# Lab_Controller_Board_v08.net
KiCad netlist of a schematic drawn in EAGLE
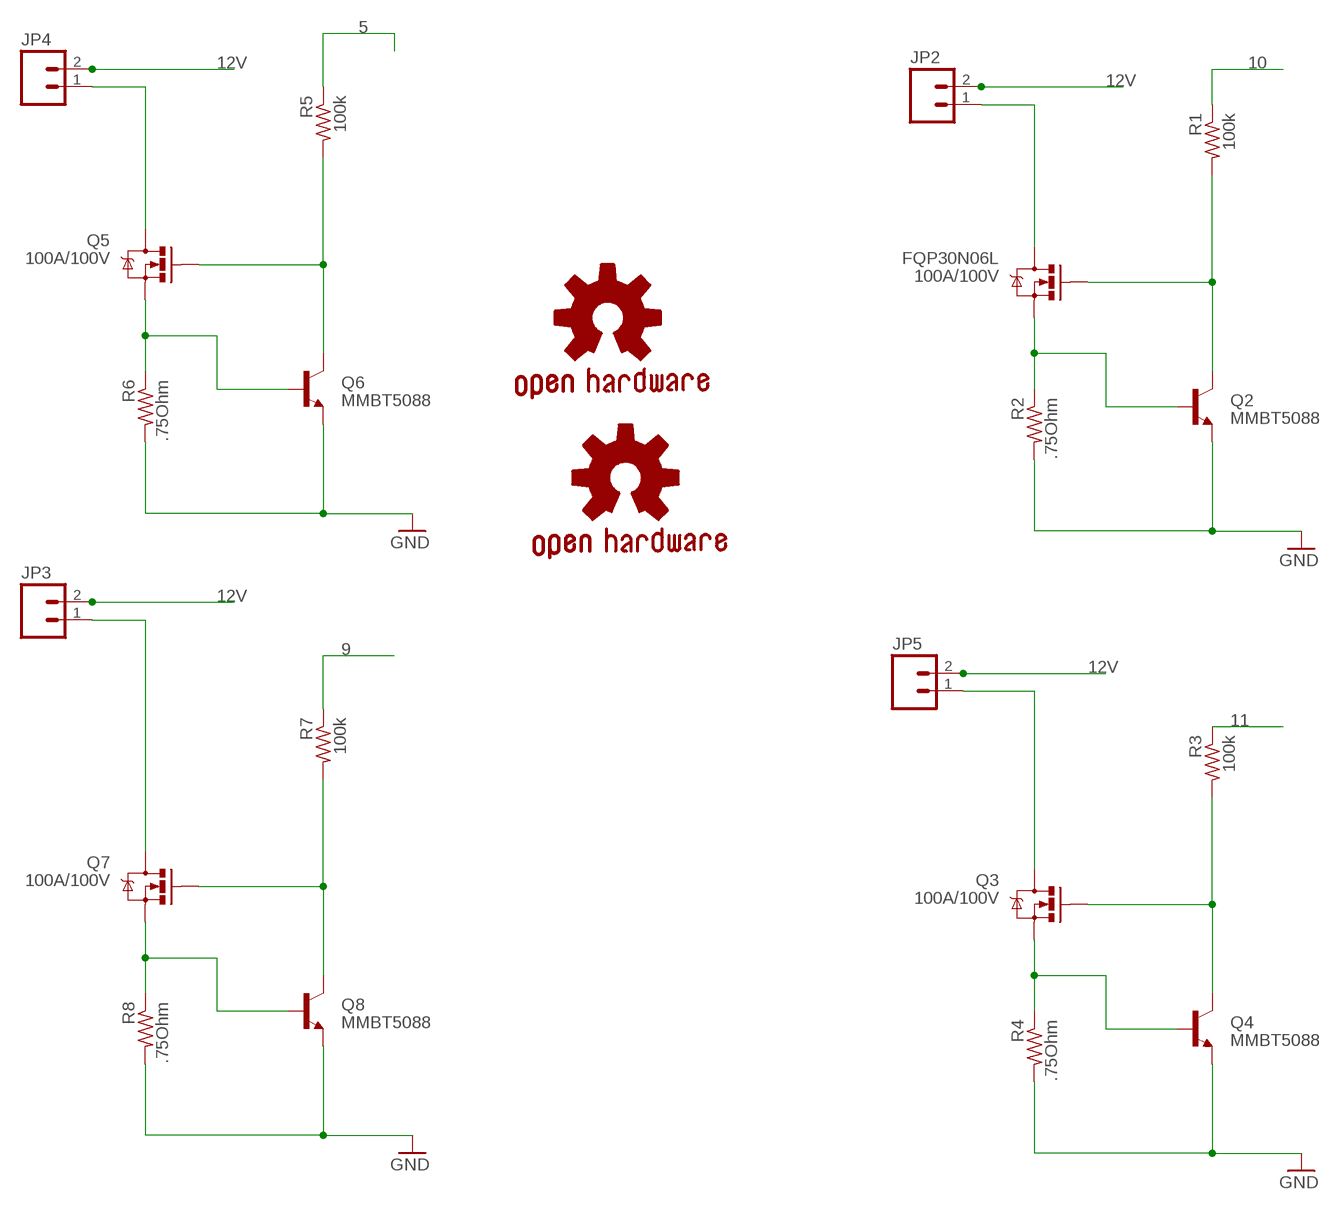
[diagram p0: schematic, sheet 1]
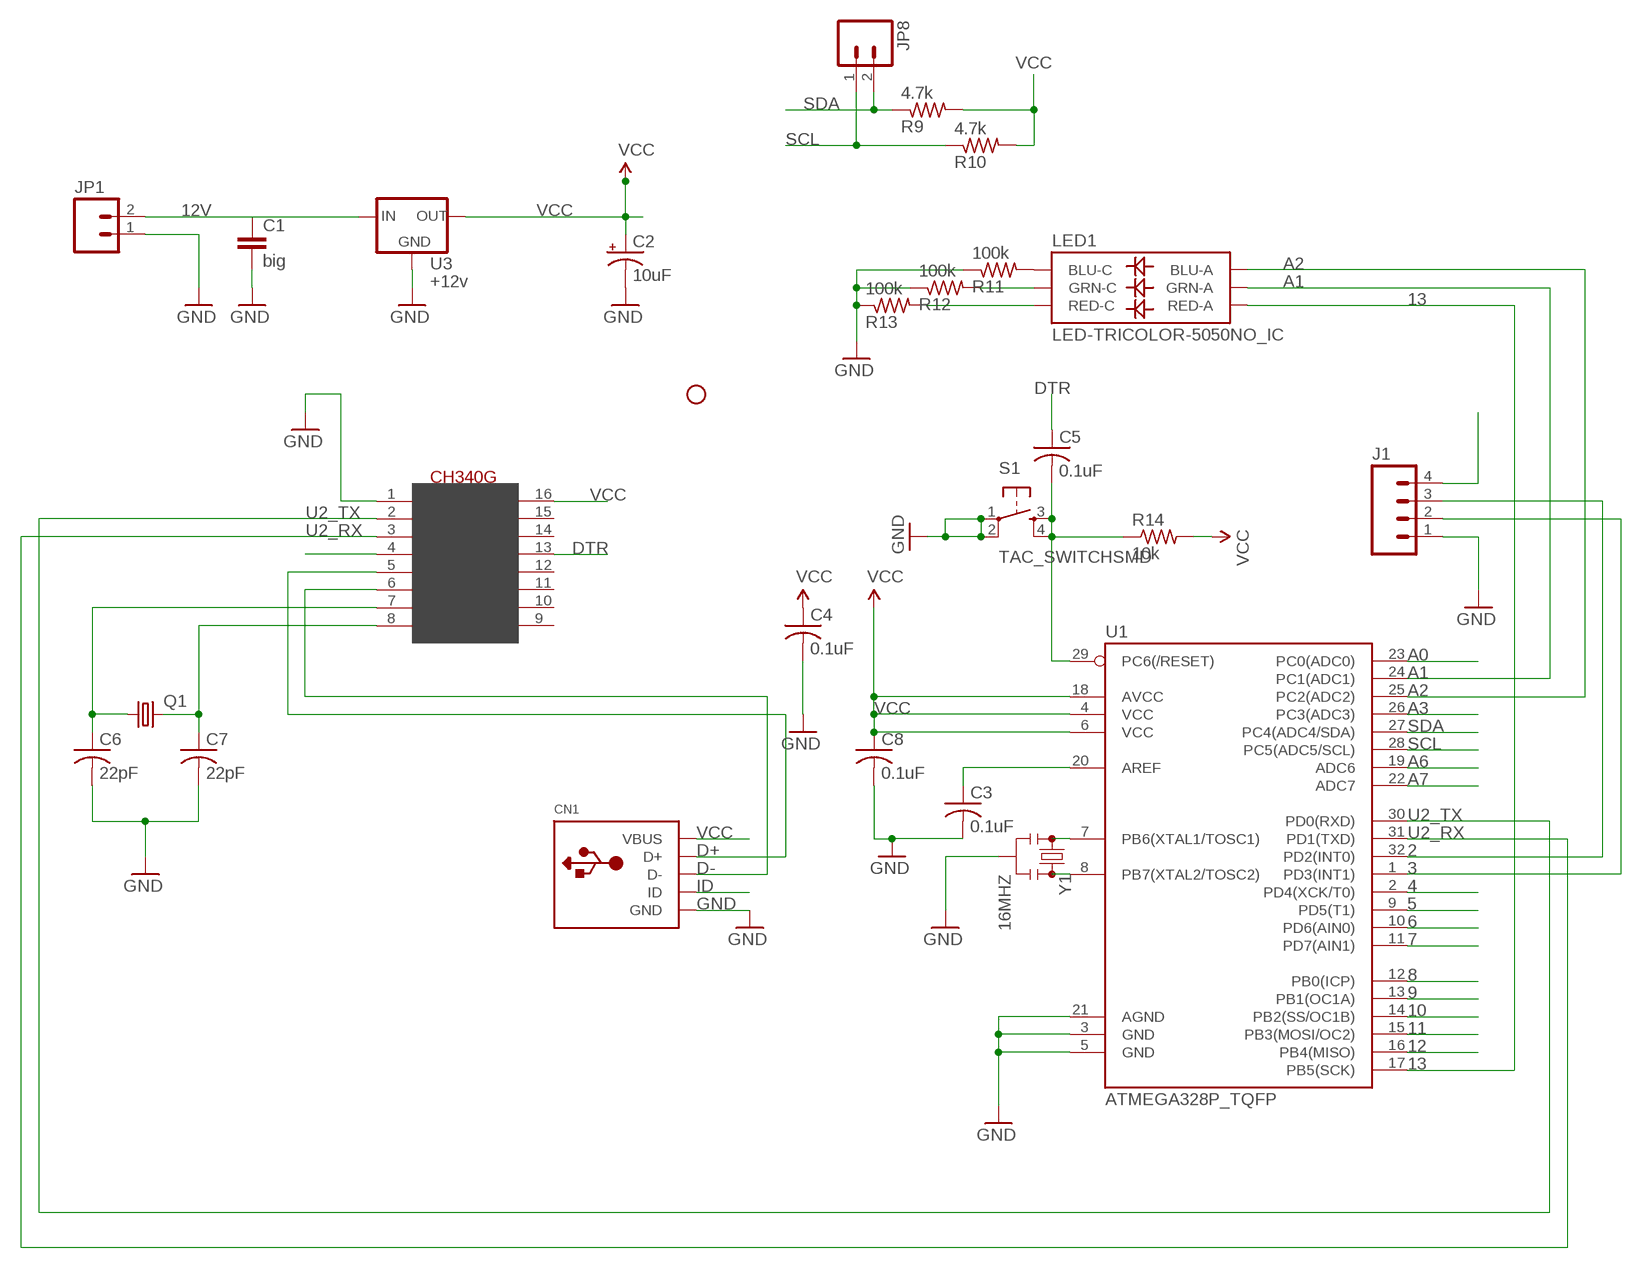
[diagram p1: schematic, sheet 2]

(export (version "E")
  (design (tool "Eeschema 10.0.6"))
  (components
    (comp (ref "C1")
      (value "big")
      (footprint "eagle-import:CAP-PTH-5MM")
      (libsource (lib "eagle-import") (part "CAPPTH1"))
    )
    (comp (ref "C2")
      (value "10uF")
      (footprint "eagle-import:EIA3528")
      (libsource (lib "eagle-import") (part "CAP_POL3528"))
    )
    (comp (ref "C3")
      (value "0.1uF")
      (footprint "eagle-import:C0402")
      (libsource (lib "eagle-import") (part "C-USC0402"))
    )
    (comp (ref "C4")
      (value "0.1uF")
      (footprint "eagle-import:C0402")
      (libsource (lib "eagle-import") (part "C-USC0402"))
    )
    (comp (ref "C5")
      (value "0.1uF")
      (footprint "eagle-import:C0402")
      (libsource (lib "eagle-import") (part "C-USC0402"))
    )
    (comp (ref "C6")
      (value "22pF")
      (footprint "eagle-import:C0402")
      (libsource (lib "eagle-import") (part "C-USC0402"))
    )
    (comp (ref "C7")
      (value "22pF")
      (footprint "eagle-import:C0402")
      (libsource (lib "eagle-import") (part "C-USC0402"))
    )
    (comp (ref "C8")
      (value "0.1uF")
      (footprint "eagle-import:C0402")
      (libsource (lib "eagle-import") (part "C-USC0402"))
    )
    (comp (ref "CN1")
      (value "USBMINIB")
      (footprint "eagle-import:USB-MINIB")
      (libsource (lib "eagle-import") (part "USBMINIB"))
    )
    (comp (ref "J1")
      (value "M04LOCK")
      (footprint "eagle-import:1X04_LOCK")
      (libsource (lib "eagle-import") (part "M04LOCK"))
    )
    (comp (ref "JP1")
      (value "M025MM")
      (footprint "eagle-import:SCREWTERMINAL-5MM-2")
      (libsource (lib "eagle-import") (part "M025MM"))
    )
    (comp (ref "JP8")
      (value "M02LOCK")
      (footprint "eagle-import:1X02_LOCK")
      (libsource (lib "eagle-import") (part "M02LOCK"))
    )
    (comp (ref "LED1")
      (value "LED-TRICOLOR-5050NO_IC")
      (footprint "eagle-import:LED-TRICOLOR-5050")
      (libsource (lib "eagle-import") (part "LED-TRICOLOR-5050NO_IC"))
    )
    (comp (ref "Q1")
      (value "CRYSTALHC49UP")
      (footprint "eagle-import:HC49UP")
      (libsource (lib "eagle-import") (part "CRYSTALHC49UP"))
    )
    (comp (ref "R9")
      (value "4.7k")
      (footprint "eagle-import:M0805")
      (libsource (lib "eagle-import") (part "R-US_M0805"))
    )
    (comp (ref "R10")
      (value "4.7k")
      (footprint "eagle-import:M0805")
      (libsource (lib "eagle-import") (part "R-US_M0805"))
    )
    (comp (ref "R11")
      (value "100k")
      (footprint "eagle-import:R0805W")
      (libsource (lib "eagle-import") (part "R-US_R0805W"))
    )
    (comp (ref "R12")
      (value "100k")
      (footprint "eagle-import:R0805W")
      (libsource (lib "eagle-import") (part "R-US_R0805W"))
    )
    (comp (ref "R13")
      (value "100k")
      (footprint "eagle-import:R0805W")
      (libsource (lib "eagle-import") (part "R-US_R0805W"))
    )
    (comp (ref "R14")
      (value "10k")
      (footprint "eagle-import:R0402")
      (libsource (lib "eagle-import") (part "R-US_R0402"))
    )
    (comp (ref "S1")
      (value "TAC_SWITCHSMD")
      (footprint "eagle-import:TACTILE-SWITCH-SMD")
      (libsource (lib "eagle-import") (part "TAC_SWITCHSMD"))
    )
    (comp (ref "STANDOFF1")
      (value "STAND-OFF")
      (footprint "eagle-import:STAND-OFF")
      (libsource (lib "eagle-import") (part "STAND-OFF"))
    )
    (comp (ref "U1")
      (value "ATMEGA328P_TQFP")
      (footprint "eagle-import:TQFP32-08")
      (libsource (lib "eagle-import") (part "ATMEGA328P_TQFP"))
    )
    (comp (ref "U2")
      (value "CH340G")
      (footprint "eagle-import:SOIC16")
      (libsource (lib "eagle-import") (part "CH340G"))
    )
    (comp (ref "U3")
      (value "+12v")
      (footprint "eagle-import:TO-252")
      (libsource (lib "eagle-import") (part "V_REG_78XX7812"))
    )
    (comp (ref "Y1")
      (value "16MHZ")
      (footprint "eagle-import:RESONATOR-SMD")
      (libsource (lib "eagle-import") (part "RESONATOR16MHZ"))
    )
    (comp (ref "FQP30N06L")
      (value "100A/100V")
      (footprint "eagle-import:TO-263_D2PAK")
      (libsource (lib "eagle-import") (part "MOSFET-NCHANNELPSMN7R0"))
    )
    (comp (ref "GOLD_ORB_SM1")
      (value "OSHWLOGO_GOLD_ORB_MED")
      (footprint "eagle-import:OSHW1")
      (libsource (lib "eagle-import") (part "OSHWLOGO_GOLD_ORB_MED"))
    )
    (comp (ref "GOLD_ORB_SM2")
      (value "OSHWLOGO_GOLD_ORB_SM")
      (footprint "eagle-import:OSHW2")
      (libsource (lib "eagle-import") (part "OSHWLOGO_GOLD_ORB_SM"))
    )
    (comp (ref "JP2")
      (value "M025MM")
      (footprint "eagle-import:SCREWTERMINAL-5MM-2")
      (libsource (lib "eagle-import") (part "M025MM"))
    )
    (comp (ref "JP3")
      (value "M025MM")
      (footprint "eagle-import:SCREWTERMINAL-5MM-2")
      (libsource (lib "eagle-import") (part "M025MM"))
    )
    (comp (ref "JP4")
      (value "M025MM")
      (footprint "eagle-import:SCREWTERMINAL-5MM-2")
      (libsource (lib "eagle-import") (part "M025MM"))
    )
    (comp (ref "JP5")
      (value "M025MM")
      (footprint "eagle-import:SCREWTERMINAL-5MM-2")
      (libsource (lib "eagle-import") (part "M025MM"))
    )
    (comp (ref "Q2")
      (value "MMBT5088")
      (footprint "eagle-import:SOT23-3")
      (libsource (lib "eagle-import") (part "TRANSISTOR_NPNMMBT5088"))
    )
    (comp (ref "Q3")
      (value "100A/100V")
      (footprint "eagle-import:TO-263_D2PAK")
      (libsource (lib "eagle-import") (part "MOSFET-NCHANNELPSMN7R0"))
    )
    (comp (ref "Q4")
      (value "MMBT5088")
      (footprint "eagle-import:SOT23-3")
      (libsource (lib "eagle-import") (part "TRANSISTOR_NPNMMBT5088"))
    )
    (comp (ref "Q5")
      (value "100A/100V")
      (footprint "eagle-import:TO-263_D2PAK")
      (libsource (lib "eagle-import") (part "MOSFET-NCHANNELPSMN7R0"))
    )
    (comp (ref "Q6")
      (value "MMBT5088")
      (footprint "eagle-import:SOT23-3")
      (libsource (lib "eagle-import") (part "TRANSISTOR_NPNMMBT5088"))
    )
    (comp (ref "Q7")
      (value "100A/100V")
      (footprint "eagle-import:TO-263_D2PAK")
      (libsource (lib "eagle-import") (part "MOSFET-NCHANNELPSMN7R0"))
    )
    (comp (ref "Q8")
      (value "MMBT5088")
      (footprint "eagle-import:SOT23-3")
      (libsource (lib "eagle-import") (part "TRANSISTOR_NPNMMBT5088"))
    )
    (comp (ref "R1")
      (value "100k")
      (footprint "eagle-import:R0805W")
      (libsource (lib "eagle-import") (part "R-US_R0805W"))
    )
    (comp (ref "R2")
      (value ".75Ohm")
      (footprint "eagle-import:0411V")
      (libsource (lib "eagle-import") (part "R-US_0411/3V"))
    )
    (comp (ref "R3")
      (value "100k")
      (footprint "eagle-import:R0805W")
      (libsource (lib "eagle-import") (part "R-US_R0805W"))
    )
    (comp (ref "R4")
      (value ".75Ohm")
      (footprint "eagle-import:0411V")
      (libsource (lib "eagle-import") (part "R-US_0411/3V"))
    )
    (comp (ref "R5")
      (value "100k")
      (footprint "eagle-import:R0805W")
      (libsource (lib "eagle-import") (part "R-US_R0805W"))
    )
    (comp (ref "R6")
      (value ".75Ohm")
      (footprint "eagle-import:0411V")
      (libsource (lib "eagle-import") (part "R-US_0411/3V"))
    )
    (comp (ref "R7")
      (value "100k")
      (footprint "eagle-import:R0805W")
      (libsource (lib "eagle-import") (part "R-US_R0805W"))
    )
    (comp (ref "R8")
      (value ".75Ohm")
      (footprint "eagle-import:0411V")
      (libsource (lib "eagle-import") (part "R-US_0411/3V"))
    )
  )
  (nets
    (net (code "1") (name "2") (class "Default")
      (node (ref "J1") (pin "3") (pinfunction "3_3") (pintype "passive"))
      (node (ref "U1") (pin "32") (pinfunction "PD2(INT0)_32") (pintype "bidirectional"))
    )
    (net (code "2") (name "3") (class "Default")
      (node (ref "J1") (pin "2") (pinfunction "2_2") (pintype "passive"))
      (node (ref "U1") (pin "1") (pinfunction "PD3(INT1)_1") (pintype "bidirectional"))
    )
    (net (code "3") (name "4") (class "Default")
      (node (ref "U1") (pin "2") (pinfunction "PD4(XCK/T0)_2") (pintype "bidirectional"))
    )
    (net (code "4") (name "5") (class "Default")
      (node (ref "R5") (pin "1") (pinfunction "1_1") (pintype "passive"))
      (node (ref "U1") (pin "9") (pinfunction "PD5(T1)_9") (pintype "bidirectional"))
    )
    (net (code "5") (name "6") (class "Default")
      (node (ref "U1") (pin "10") (pinfunction "PD6(AIN0)_10") (pintype "bidirectional"))
    )
    (net (code "6") (name "7") (class "Default")
      (node (ref "U1") (pin "11") (pinfunction "PD7(AIN1)_11") (pintype "bidirectional"))
    )
    (net (code "7") (name "8") (class "Default")
      (node (ref "U1") (pin "12") (pinfunction "PB0(ICP)_12") (pintype "bidirectional"))
    )
    (net (code "8") (name "9") (class "Default")
      (node (ref "R7") (pin "1") (pinfunction "1_1") (pintype "passive"))
      (node (ref "U1") (pin "13") (pinfunction "PB1(OC1A)_13") (pintype "bidirectional"))
    )
    (net (code "9") (name "10") (class "Default")
      (node (ref "R1") (pin "1") (pinfunction "1_1") (pintype "passive"))
      (node (ref "U1") (pin "14") (pinfunction "PB2(SS/OC1B)_14") (pintype "bidirectional"))
    )
    (net (code "10") (name "11") (class "Default")
      (node (ref "R3") (pin "1") (pinfunction "1_1") (pintype "passive"))
      (node (ref "U1") (pin "15") (pinfunction "PB3(MOSI/OC2)_15") (pintype "bidirectional"))
    )
    (net (code "11") (name "12") (class "Default")
      (node (ref "U1") (pin "16") (pinfunction "PB4(MISO)_16") (pintype "bidirectional"))
    )
    (net (code "12") (name "12V") (class "Default")
      (node (ref "C1") (pin "1") (pinfunction "1_1") (pintype "passive"))
      (node (ref "JP1") (pin "2") (pinfunction "2_2") (pintype "passive"))
      (node (ref "JP2") (pin "2") (pinfunction "2_2") (pintype "passive"))
      (node (ref "JP3") (pin "2") (pinfunction "2_2") (pintype "passive"))
      (node (ref "JP4") (pin "2") (pinfunction "2_2") (pintype "passive"))
      (node (ref "JP5") (pin "2") (pinfunction "2_2") (pintype "passive"))
      (node (ref "U3") (pin "1") (pinfunction "IN_1") (pintype "input"))
    )
    (net (code "13") (name "13") (class "Default")
      (node (ref "LED1") (pin "2") (pinfunction "RED-A_2") (pintype "bidirectional"))
      (node (ref "U1") (pin "17") (pinfunction "PB5(SCK)_17") (pintype "bidirectional"))
    )
    (net (code "14") (name "A0") (class "Default")
      (node (ref "U1") (pin "23") (pinfunction "PC0(ADC0)_23") (pintype "bidirectional"))
    )
    (net (code "15") (name "A1") (class "Default")
      (node (ref "LED1") (pin "1") (pinfunction "GRN-A_1") (pintype "bidirectional"))
      (node (ref "U1") (pin "24") (pinfunction "PC1(ADC1)_24") (pintype "bidirectional"))
    )
    (net (code "16") (name "A2") (class "Default")
      (node (ref "LED1") (pin "3") (pinfunction "BLU-A_3") (pintype "bidirectional"))
      (node (ref "U1") (pin "25") (pinfunction "PC2(ADC2)_25") (pintype "bidirectional"))
    )
    (net (code "17") (name "A3") (class "Default")
      (node (ref "U1") (pin "26") (pinfunction "PC3(ADC3)_26") (pintype "bidirectional"))
    )
    (net (code "18") (name "A6") (class "Default")
      (node (ref "U1") (pin "19") (pinfunction "ADC6_19") (pintype "bidirectional"))
    )
    (net (code "19") (name "A7") (class "Default")
      (node (ref "U1") (pin "22") (pinfunction "ADC7_22") (pintype "bidirectional"))
    )
    (net (code "20") (name "D+") (class "Default")
      (node (ref "CN1") (pin "D+") (pinfunction "D+_D+") (pintype "bidirectional"))
      (node (ref "U2") (pin "5") (pinfunction "D+_5") (pintype "bidirectional"))
    )
    (net (code "21") (name "D-") (class "Default")
      (node (ref "CN1") (pin "D-") (pinfunction "D-_D-") (pintype "bidirectional"))
      (node (ref "U2") (pin "6") (pinfunction "D-_6") (pintype "bidirectional"))
    )
    (net (code "22") (name "DTR") (class "Default")
      (node (ref "C5") (pin "1") (pinfunction "1_1") (pintype "passive"))
      (node (ref "U2") (pin "13") (pinfunction "DTR_13") (pintype "bidirectional"))
    )
    (net (code "23") (name "GND") (class "Default")
      (node (ref "C1") (pin "2") (pinfunction "2_2") (pintype "passive"))
      (node (ref "C2") (pin "C") (pinfunction "-_C") (pintype "passive"))
      (node (ref "C3") (pin "2") (pinfunction "2_2") (pintype "passive"))
      (node (ref "C4") (pin "2") (pinfunction "2_2") (pintype "passive"))
      (node (ref "C6") (pin "2") (pinfunction "2_2") (pintype "passive"))
      (node (ref "C7") (pin "2") (pinfunction "2_2") (pintype "passive"))
      (node (ref "C8") (pin "2") (pinfunction "2_2") (pintype "passive"))
      (node (ref "CN1") (pin "GND") (pinfunction "GND_GND") (pintype "power_in"))
      (node (ref "J1") (pin "1") (pinfunction "1_1") (pintype "passive"))
      (node (ref "JP1") (pin "1") (pinfunction "1_1") (pintype "passive"))
      (node (ref "Q2") (pin "2") (pinfunction "E_2") (pintype "passive"))
      (node (ref "Q4") (pin "2") (pinfunction "E_2") (pintype "passive"))
      (node (ref "Q6") (pin "2") (pinfunction "E_2") (pintype "passive"))
      (node (ref "Q8") (pin "2") (pinfunction "E_2") (pintype "passive"))
      (node (ref "R11") (pin "1") (pinfunction "1_1") (pintype "passive"))
      (node (ref "R12") (pin "1") (pinfunction "1_1") (pintype "passive"))
      (node (ref "R13") (pin "1") (pinfunction "1_1") (pintype "passive"))
      (node (ref "R2") (pin "2") (pinfunction "2_2") (pintype "passive"))
      (node (ref "R4") (pin "2") (pinfunction "2_2") (pintype "passive"))
      (node (ref "R6") (pin "2") (pinfunction "2_2") (pintype "passive"))
      (node (ref "R8") (pin "2") (pinfunction "2_2") (pintype "passive"))
      (node (ref "S1") (pin "1") (pinfunction "1_1") (pintype "passive"))
      (node (ref "S1") (pin "2") (pinfunction "2_2") (pintype "passive"))
      (node (ref "U1") (pin "21") (pinfunction "AGND_21") (pintype "bidirectional"))
      (node (ref "U1") (pin "3") (pinfunction "GND_3") (pintype "bidirectional"))
      (node (ref "U1") (pin "5") (pinfunction "GND_5") (pintype "bidirectional"))
      (node (ref "U2") (pin "1") (pinfunction "GND_1") (pintype "bidirectional"))
      (node (ref "U3") (pin "3") (pinfunction "GND_3") (pintype "input"))
      (node (ref "Y1") (pin "2") (pinfunction "2_2") (pintype "passive"))
    )
    (net (code "24") (name "ID") (class "Default")
      (node (ref "CN1") (pin "ID") (pinfunction "ID_ID") (pintype "bidirectional"))
    )
    (net (code "25") (name "Net-(FQP30N06L-D)") (class "Default")
      (node (ref "FQP30N06L") (pin "2") (pinfunction "D_2") (pintype "passive"))
      (node (ref "JP2") (pin "1") (pinfunction "1_1") (pintype "passive"))
    )
    (net (code "26") (name "Net-(FQP30N06L-G)") (class "Default")
      (node (ref "FQP30N06L") (pin "1") (pinfunction "G_1") (pintype "passive"))
      (node (ref "Q2") (pin "3") (pinfunction "C_3") (pintype "passive"))
      (node (ref "R1") (pin "2") (pinfunction "2_2") (pintype "passive"))
    )
    (net (code "27") (name "Net-(FQP30N06L-S)") (class "Default")
      (node (ref "FQP30N06L") (pin "3") (pinfunction "S_3") (pintype "passive"))
      (node (ref "Q2") (pin "1") (pinfunction "B_1") (pintype "passive"))
      (node (ref "R2") (pin "1") (pinfunction "1_1") (pintype "passive"))
    )
    (net (code "28") (name "Net-(LED1-BLU-C)") (class "Default")
      (node (ref "LED1") (pin "4") (pinfunction "BLU-C_4") (pintype "bidirectional"))
      (node (ref "R11") (pin "2") (pinfunction "2_2") (pintype "passive"))
    )
    (net (code "29") (name "Net-(LED1-GRN-C)") (class "Default")
      (node (ref "LED1") (pin "6") (pinfunction "GRN-C_6") (pintype "bidirectional"))
      (node (ref "R12") (pin "2") (pinfunction "2_2") (pintype "passive"))
    )
    (net (code "30") (name "Net-(LED1-RED-C)") (class "Default")
      (node (ref "LED1") (pin "5") (pinfunction "RED-C_5") (pintype "bidirectional"))
      (node (ref "R13") (pin "2") (pinfunction "2_2") (pintype "passive"))
    )
    (net (code "31") (name "Net-(Q3-D)") (class "Default")
      (node (ref "JP5") (pin "1") (pinfunction "1_1") (pintype "passive"))
      (node (ref "Q3") (pin "2") (pinfunction "D_2") (pintype "passive"))
    )
    (net (code "32") (name "Net-(Q3-G)") (class "Default")
      (node (ref "Q3") (pin "1") (pinfunction "G_1") (pintype "passive"))
      (node (ref "Q4") (pin "3") (pinfunction "C_3") (pintype "passive"))
      (node (ref "R3") (pin "2") (pinfunction "2_2") (pintype "passive"))
    )
    (net (code "33") (name "Net-(Q3-S)") (class "Default")
      (node (ref "Q3") (pin "3") (pinfunction "S_3") (pintype "passive"))
      (node (ref "Q4") (pin "1") (pinfunction "B_1") (pintype "passive"))
      (node (ref "R4") (pin "1") (pinfunction "1_1") (pintype "passive"))
    )
    (net (code "34") (name "Net-(Q5-D)") (class "Default")
      (node (ref "JP4") (pin "1") (pinfunction "1_1") (pintype "passive"))
      (node (ref "Q5") (pin "2") (pinfunction "D_2") (pintype "passive"))
    )
    (net (code "35") (name "Net-(Q5-G)") (class "Default")
      (node (ref "Q5") (pin "1") (pinfunction "G_1") (pintype "passive"))
      (node (ref "Q6") (pin "3") (pinfunction "C_3") (pintype "passive"))
      (node (ref "R5") (pin "2") (pinfunction "2_2") (pintype "passive"))
    )
    (net (code "36") (name "Net-(Q5-S)") (class "Default")
      (node (ref "Q5") (pin "3") (pinfunction "S_3") (pintype "passive"))
      (node (ref "Q6") (pin "1") (pinfunction "B_1") (pintype "passive"))
      (node (ref "R6") (pin "1") (pinfunction "1_1") (pintype "passive"))
    )
    (net (code "37") (name "Net-(Q7-D)") (class "Default")
      (node (ref "JP3") (pin "1") (pinfunction "1_1") (pintype "passive"))
      (node (ref "Q7") (pin "2") (pinfunction "D_2") (pintype "passive"))
    )
    (net (code "38") (name "Net-(Q7-G)") (class "Default")
      (node (ref "Q7") (pin "1") (pinfunction "G_1") (pintype "passive"))
      (node (ref "Q8") (pin "3") (pinfunction "C_3") (pintype "passive"))
      (node (ref "R7") (pin "2") (pinfunction "2_2") (pintype "passive"))
    )
    (net (code "39") (name "Net-(Q7-S)") (class "Default")
      (node (ref "Q7") (pin "3") (pinfunction "S_3") (pintype "passive"))
      (node (ref "Q8") (pin "1") (pinfunction "B_1") (pintype "passive"))
      (node (ref "R8") (pin "1") (pinfunction "1_1") (pintype "passive"))
    )
    (net (code "40") (name "Net-(U1-AREF)") (class "Default")
      (node (ref "C3") (pin "1") (pinfunction "1_1") (pintype "passive"))
      (node (ref "U1") (pin "20") (pinfunction "AREF_20") (pintype "bidirectional"))
    )
    (net (code "41") (name "Net-(U1-PB6(XTAL1{slash}TOSC1))") (class "Default")
      (node (ref "U1") (pin "7") (pinfunction "PB6(XTAL1/TOSC1)_7") (pintype "bidirectional"))
      (node (ref "Y1") (pin "1") (pinfunction "1_1") (pintype "passive"))
    )
    (net (code "42") (name "Net-(U1-PB7(XTAL2{slash}TOSC2))") (class "Default")
      (node (ref "U1") (pin "8") (pinfunction "PB7(XTAL2/TOSC2)_8") (pintype "bidirectional"))
      (node (ref "Y1") (pin "3") (pinfunction "3_3") (pintype "passive"))
    )
    (net (code "43") (name "Net-(U1-PC6({slash}RESET))") (class "Default")
      (node (ref "C5") (pin "2") (pinfunction "2_2") (pintype "passive"))
      (node (ref "R14") (pin "1") (pinfunction "1_1") (pintype "passive"))
      (node (ref "S1") (pin "3") (pinfunction "3_3") (pintype "passive"))
      (node (ref "S1") (pin "4") (pinfunction "4_4") (pintype "passive"))
      (node (ref "U1") (pin "29") (pinfunction "PC6(/RESET)_29") (pintype "bidirectional"))
    )
    (net (code "44") (name "Net-(U2-XI)") (class "Default")
      (node (ref "C6") (pin "1") (pinfunction "1_1") (pintype "passive"))
      (node (ref "Q1") (pin "1") (pinfunction "1_1") (pintype "passive"))
      (node (ref "U2") (pin "7") (pinfunction "XI_7") (pintype "bidirectional"))
    )
    (net (code "45") (name "Net-(U2-XO)") (class "Default")
      (node (ref "C7") (pin "1") (pinfunction "1_1") (pintype "passive"))
      (node (ref "Q1") (pin "2") (pinfunction "2_2") (pintype "passive"))
      (node (ref "U2") (pin "8") (pinfunction "XO_8") (pintype "bidirectional"))
    )
    (net (code "46") (name "SCL") (class "Default")
      (node (ref "JP8") (pin "1") (pinfunction "1_1") (pintype "passive"))
      (node (ref "R10") (pin "1") (pinfunction "1_1") (pintype "passive"))
      (node (ref "U1") (pin "28") (pinfunction "PC5(ADC5/SCL)_28") (pintype "bidirectional"))
    )
    (net (code "47") (name "SDA") (class "Default")
      (node (ref "JP8") (pin "2") (pinfunction "2_2") (pintype "passive"))
      (node (ref "R9") (pin "1") (pinfunction "1_1") (pintype "passive"))
      (node (ref "U1") (pin "27") (pinfunction "PC4(ADC4/SDA)_27") (pintype "bidirectional"))
    )
    (net (code "48") (name "U2_RX") (class "Default")
      (node (ref "U1") (pin "31") (pinfunction "PD1(TXD)_31") (pintype "bidirectional"))
      (node (ref "U2") (pin "3") (pinfunction "RX_3") (pintype "bidirectional"))
    )
    (net (code "49") (name "U2_TX") (class "Default")
      (node (ref "U1") (pin "30") (pinfunction "PD0(RXD)_30") (pintype "bidirectional"))
      (node (ref "U2") (pin "2") (pinfunction "TX_2") (pintype "bidirectional"))
    )
    (net (code "50") (name "VCC") (class "Default")
      (node (ref "C2") (pin "A") (pinfunction "+_A") (pintype "passive"))
      (node (ref "C4") (pin "1") (pinfunction "1_1") (pintype "passive"))
      (node (ref "C8") (pin "1") (pinfunction "1_1") (pintype "passive"))
      (node (ref "CN1") (pin "VBUS") (pinfunction "VBUS_VBUS") (pintype "power_in"))
      (node (ref "J1") (pin "4") (pinfunction "4_4") (pintype "passive"))
      (node (ref "R10") (pin "2") (pinfunction "2_2") (pintype "passive"))
      (node (ref "R14") (pin "2") (pinfunction "2_2") (pintype "passive"))
      (node (ref "R9") (pin "2") (pinfunction "2_2") (pintype "passive"))
      (node (ref "U1") (pin "18") (pinfunction "AVCC_18") (pintype "bidirectional"))
      (node (ref "U1") (pin "4") (pinfunction "VCC_4") (pintype "bidirectional"))
      (node (ref "U1") (pin "6") (pinfunction "VCC_6") (pintype "bidirectional"))
      (node (ref "U2") (pin "16") (pinfunction "VCC_16") (pintype "bidirectional"))
      (node (ref "U3") (pin "2") (pinfunction "OUT_2") (pintype "passive"))
    )
    (net (code "51") (name "unconnected-(U2-CTS-Pad9)") (class "Default")
      (node (ref "U2") (pin "9") (pinfunction "CTS_9") (pintype "bidirectional"))
    )
    (net (code "52") (name "unconnected-(U2-DCD-Pad12)") (class "Default")
      (node (ref "U2") (pin "12") (pinfunction "DCD_12") (pintype "bidirectional"))
    )
    (net (code "53") (name "unconnected-(U2-DSR-Pad10)") (class "Default")
      (node (ref "U2") (pin "10") (pinfunction "DSR_10") (pintype "bidirectional"))
    )
    (net (code "54") (name "unconnected-(U2-RI-Pad11)") (class "Default")
      (node (ref "U2") (pin "11") (pinfunction "RI_11") (pintype "bidirectional"))
    )
    (net (code "55") (name "unconnected-(U2-RS232-Pad15)") (class "Default")
      (node (ref "U2") (pin "15") (pinfunction "RS232_15") (pintype "bidirectional"))
    )
    (net (code "56") (name "unconnected-(U2-RTS-Pad14)") (class "Default")
      (node (ref "U2") (pin "14") (pinfunction "RTS_14") (pintype "bidirectional"))
    )
    (net (code "57") (name "unconnected-(U2-V3-Pad4)") (class "Default")
      (node (ref "U2") (pin "4") (pinfunction "V3_4") (pintype "bidirectional"))
    )
  )
)
